# myPowerSatBoard.net
KiCad netlist of a schematic drawn in EAGLE
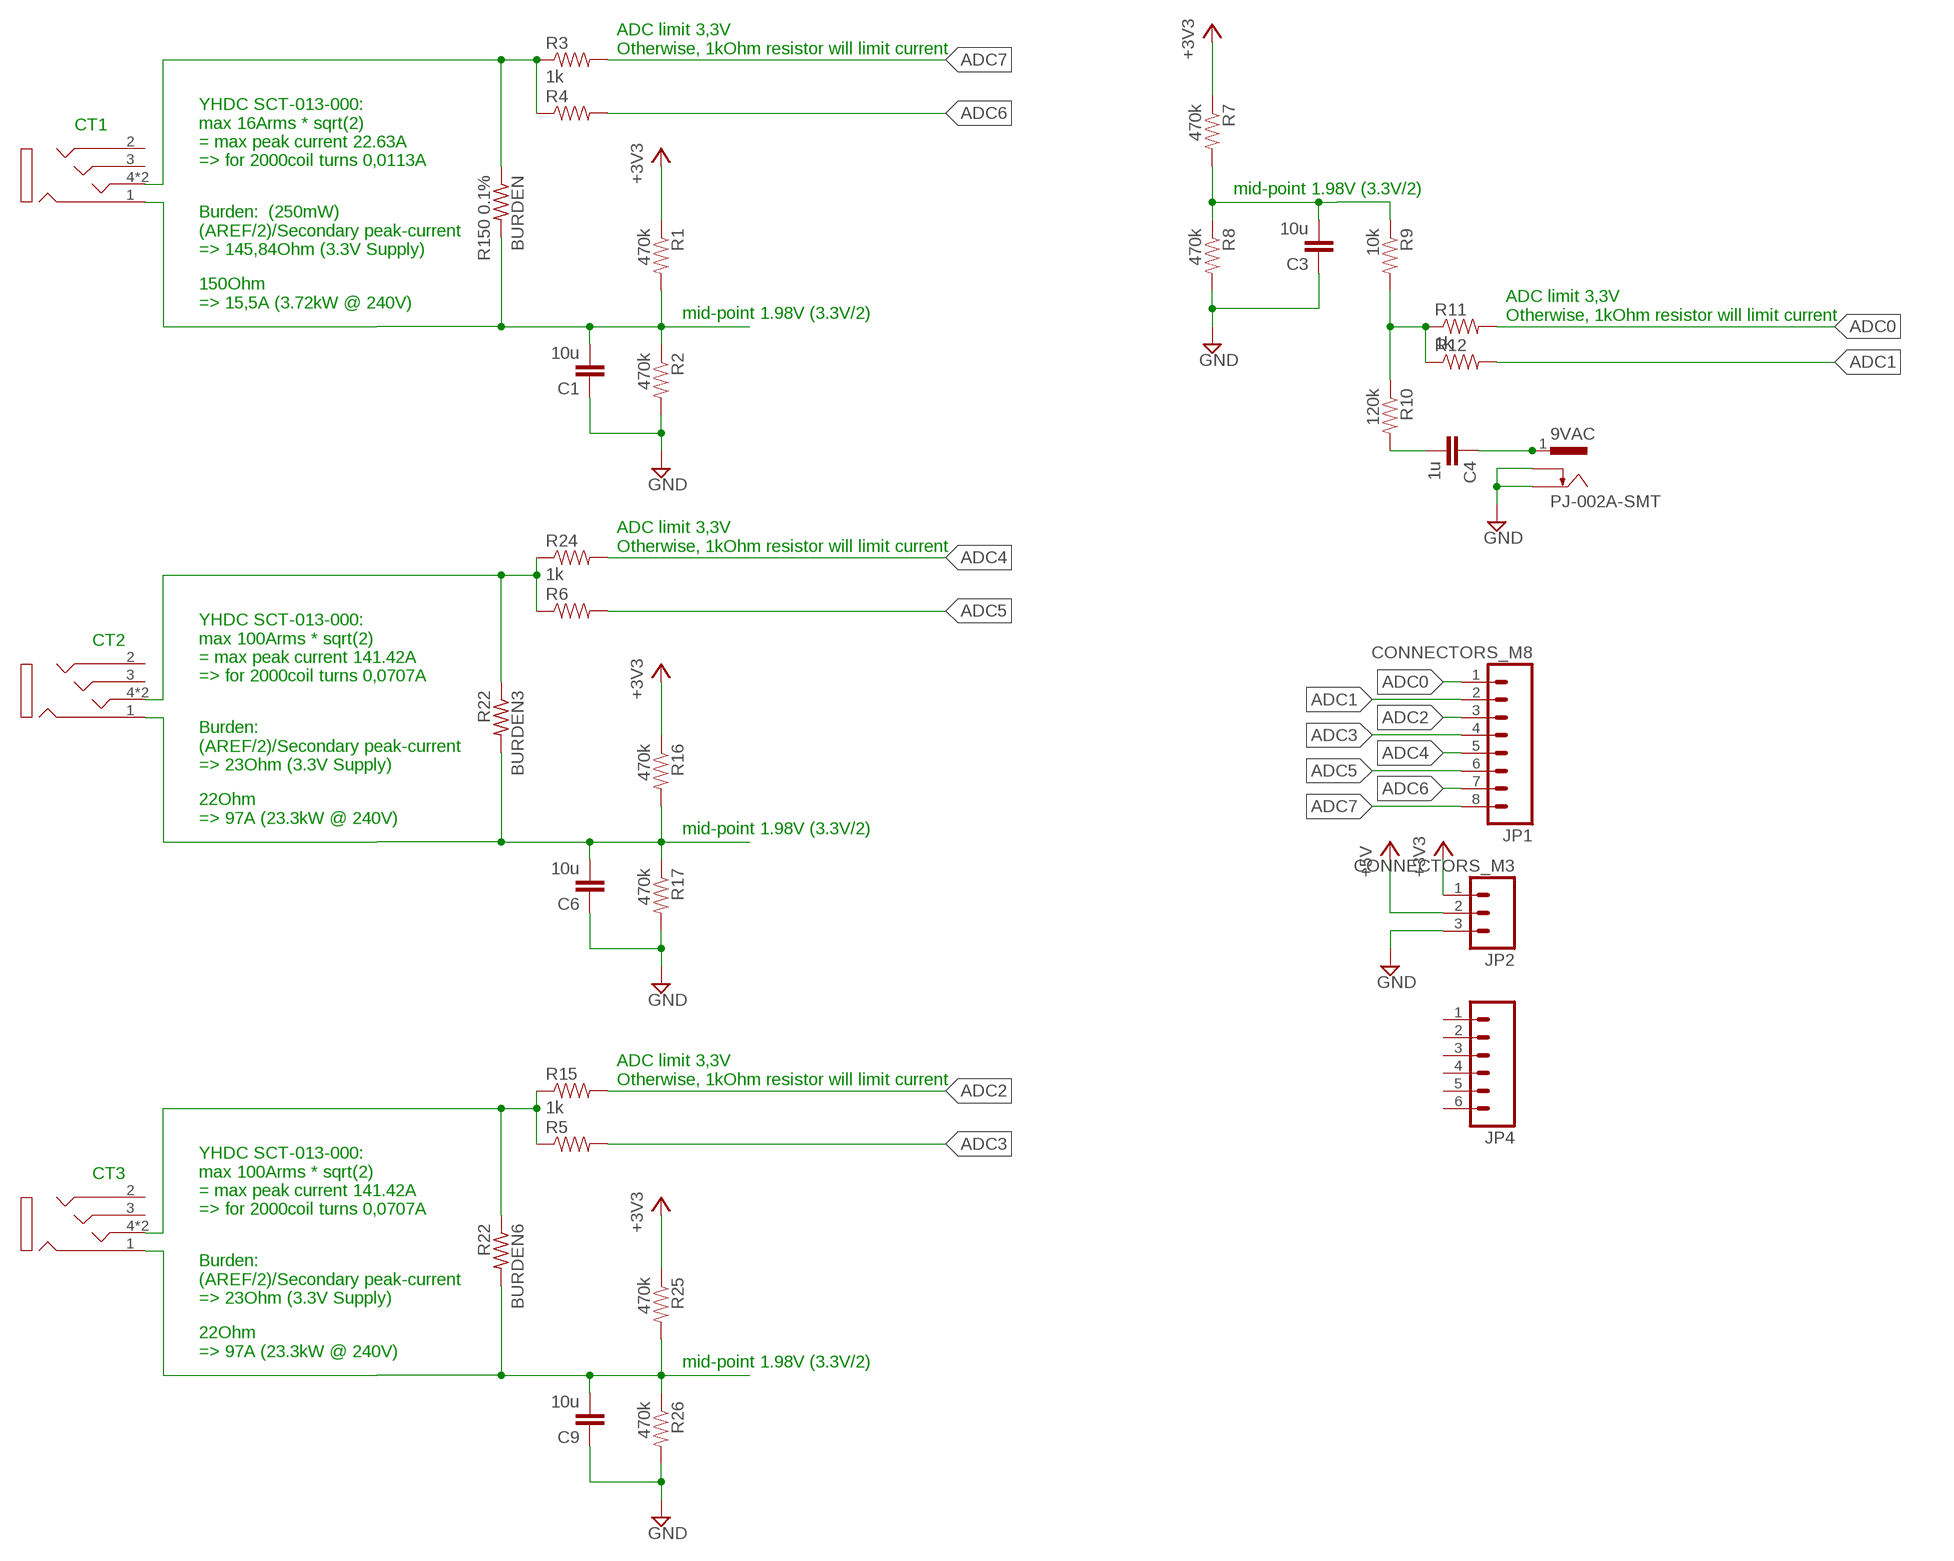
[diagram p0: schematic, sheet 1]

(export (version "E")
  (design (tool "Eeschema 10.0.6"))
  (components
    (comp (ref "9VAC")
      (value "PJ-002A-SMT")
      (footprint "eagle-import:CUI_PJ-002B-SMT")
      (libsource (lib "eagle-import") (part "PJ-002A-SMT"))
    )
    (comp (ref "BURDEN")
      (value "R150 0.1%")
      (footprint "eagle-import:R0805")
      (libsource (lib "eagle-import") (part "R-US_R0805"))
    )
    (comp (ref "BURDEN3")
      (value "R22")
      (footprint "eagle-import:R0805")
      (libsource (lib "eagle-import") (part "R-US_R0805"))
    )
    (comp (ref "BURDEN6")
      (value "R22")
      (footprint "eagle-import:R0805")
      (libsource (lib "eagle-import") (part "R-US_R0805"))
    )
    (comp (ref "C1")
      (value "10u")
      (footprint "eagle-import:0603-CAP")
      (libsource (lib "eagle-import") (part "CAP0603-CAP"))
    )
    (comp (ref "C3")
      (value "10u")
      (footprint "eagle-import:0603-CAP")
      (libsource (lib "eagle-import") (part "CAP0603-CAP"))
    )
    (comp (ref "C4")
      (value "1u")
      (footprint "eagle-import:0603-CAP")
      (libsource (lib "eagle-import") (part "CAP0603-CAP"))
    )
    (comp (ref "C6")
      (value "10u")
      (footprint "eagle-import:0603-CAP")
      (libsource (lib "eagle-import") (part "CAP0603-CAP"))
    )
    (comp (ref "C9")
      (value "10u")
      (footprint "eagle-import:0603-CAP")
      (libsource (lib "eagle-import") (part "CAP0603-CAP"))
    )
    (comp (ref "CT1")
      (value "1503_13")
      (footprint "eagle-import:1503-03")
      (libsource (lib "eagle-import") (part "1503_13"))
    )
    (comp (ref "CT4")
      (value "1503_13")
      (footprint "eagle-import:1503-03")
      (libsource (lib "eagle-import") (part "1503_13"))
    )
    (comp (ref "CT7")
      (value "1503_13")
      (footprint "eagle-import:1503-03")
      (libsource (lib "eagle-import") (part "1503_13"))
    )
    (comp (ref "JP1")
      (value "CONNECTORS_M8")
      (footprint "eagle-import:CONNECTORS_1X8")
      (libsource (lib "eagle-import") (part "CONNECTORS_M8"))
    )
    (comp (ref "JP2")
      (value "CONNECTORS_M3")
      (footprint "eagle-import:CONNECTORS_1X3")
      (libsource (lib "eagle-import") (part "CONNECTORS_M3"))
    )
    (comp (ref "JP4")
      (value "CONNECTORS_M06SIP")
      (footprint "eagle-import:CONNECTORS_1X06")
      (libsource (lib "eagle-import") (part "CONNECTORS_M06SIP"))
    )
    (comp (ref "R1")
      (value "470k")
      (footprint "eagle-import:0603-RES")
      (libsource (lib "eagle-import") (part "RESISTOR0603-RES"))
    )
    (comp (ref "R2")
      (value "470k")
      (footprint "eagle-import:0603-RES")
      (libsource (lib "eagle-import") (part "RESISTOR0603-RES"))
    )
    (comp (ref "R3")
      (value "1k")
      (footprint "eagle-import:0603-RES")
      (libsource (lib "eagle-import") (part "RESISTOR0603-RES"))
    )
    (comp (ref "R4")
      (value "RESISTOR0603-RES")
      (footprint "eagle-import:0603-RES")
      (libsource (lib "eagle-import") (part "RESISTOR0603-RES"))
    )
    (comp (ref "R5")
      (value "RESISTOR0603-RES")
      (footprint "eagle-import:0603-RES")
      (libsource (lib "eagle-import") (part "RESISTOR0603-RES"))
    )
    (comp (ref "R6")
      (value "RESISTOR0603-RES")
      (footprint "eagle-import:0603-RES")
      (libsource (lib "eagle-import") (part "RESISTOR0603-RES"))
    )
    (comp (ref "R7")
      (value "470k")
      (footprint "eagle-import:0603-RES")
      (libsource (lib "eagle-import") (part "RESISTOR0603-RES"))
    )
    (comp (ref "R8")
      (value "470k")
      (footprint "eagle-import:0603-RES")
      (libsource (lib "eagle-import") (part "RESISTOR0603-RES"))
    )
    (comp (ref "R9")
      (value "10k")
      (footprint "eagle-import:0603-RES")
      (libsource (lib "eagle-import") (part "RESISTOR0603-RES"))
    )
    (comp (ref "R10")
      (value "120k")
      (footprint "eagle-import:0603-RES")
      (libsource (lib "eagle-import") (part "RESISTOR0603-RES"))
    )
    (comp (ref "R11")
      (value "1k")
      (footprint "eagle-import:0603-RES")
      (libsource (lib "eagle-import") (part "RESISTOR0603-RES"))
    )
    (comp (ref "R12")
      (value "RESISTOR0603-RES")
      (footprint "eagle-import:0603-RES")
      (libsource (lib "eagle-import") (part "RESISTOR0603-RES"))
    )
    (comp (ref "R15")
      (value "1k")
      (footprint "eagle-import:0603-RES")
      (libsource (lib "eagle-import") (part "RESISTOR0603-RES"))
    )
    (comp (ref "R16")
      (value "470k")
      (footprint "eagle-import:0603-RES")
      (libsource (lib "eagle-import") (part "RESISTOR0603-RES"))
    )
    (comp (ref "R17")
      (value "470k")
      (footprint "eagle-import:0603-RES")
      (libsource (lib "eagle-import") (part "RESISTOR0603-RES"))
    )
    (comp (ref "R24")
      (value "1k")
      (footprint "eagle-import:0603-RES")
      (libsource (lib "eagle-import") (part "RESISTOR0603-RES"))
    )
    (comp (ref "R25")
      (value "470k")
      (footprint "eagle-import:0603-RES")
      (libsource (lib "eagle-import") (part "RESISTOR0603-RES"))
    )
    (comp (ref "R26")
      (value "470k")
      (footprint "eagle-import:0603-RES")
      (libsource (lib "eagle-import") (part "RESISTOR0603-RES"))
    )
  )
  (nets
    (net (code "1") (name "+3V3") (class "Default")
      (node (ref "JP2") (pin "1") (pinfunction "1_1") (pintype "passive"))
      (node (ref "R1") (pin "1") (pinfunction "1_1") (pintype "passive"))
      (node (ref "R16") (pin "1") (pinfunction "1_1") (pintype "passive"))
      (node (ref "R25") (pin "1") (pinfunction "1_1") (pintype "passive"))
      (node (ref "R7") (pin "1") (pinfunction "1_1") (pintype "passive"))
    )
    (net (code "2") (name "+5V") (class "Default")
      (node (ref "JP2") (pin "2") (pinfunction "2_2") (pintype "passive"))
    )
    (net (code "3") (name "ADC0") (class "Default")
      (node (ref "JP1") (pin "1") (pinfunction "1_1") (pintype "passive"))
      (node (ref "R11") (pin "2") (pinfunction "2_2") (pintype "passive"))
    )
    (net (code "4") (name "ADC1") (class "Default")
      (node (ref "JP1") (pin "2") (pinfunction "2_2") (pintype "passive"))
      (node (ref "R12") (pin "2") (pinfunction "2_2") (pintype "passive"))
    )
    (net (code "5") (name "ADC2") (class "Default")
      (node (ref "JP1") (pin "3") (pinfunction "3_3") (pintype "passive"))
      (node (ref "R15") (pin "2") (pinfunction "2_2") (pintype "passive"))
    )
    (net (code "6") (name "ADC3") (class "Default")
      (node (ref "JP1") (pin "4") (pinfunction "4_4") (pintype "passive"))
      (node (ref "R5") (pin "2") (pinfunction "2_2") (pintype "passive"))
    )
    (net (code "7") (name "ADC4") (class "Default")
      (node (ref "JP1") (pin "5") (pinfunction "5_5") (pintype "passive"))
      (node (ref "R24") (pin "2") (pinfunction "2_2") (pintype "passive"))
    )
    (net (code "8") (name "ADC5") (class "Default")
      (node (ref "JP1") (pin "6") (pinfunction "6_6") (pintype "passive"))
      (node (ref "R6") (pin "2") (pinfunction "2_2") (pintype "passive"))
    )
    (net (code "9") (name "ADC6") (class "Default")
      (node (ref "JP1") (pin "7") (pinfunction "7_7") (pintype "passive"))
      (node (ref "R4") (pin "2") (pinfunction "2_2") (pintype "passive"))
    )
    (net (code "10") (name "ADC7") (class "Default")
      (node (ref "JP1") (pin "8") (pinfunction "8_8") (pintype "passive"))
      (node (ref "R3") (pin "2") (pinfunction "2_2") (pintype "passive"))
    )
    (net (code "11") (name "GND") (class "Default")
      (node (ref "9VAC") (pin "3") (pinfunction "3_3") (pintype "passive"))
      (node (ref "9VAC") (pin "4") (pinfunction "4_4") (pintype "passive"))
      (node (ref "C1") (pin "1") (pinfunction "1_1") (pintype "passive"))
      (node (ref "C3") (pin "1") (pinfunction "1_1") (pintype "passive"))
      (node (ref "C6") (pin "1") (pinfunction "1_1") (pintype "passive"))
      (node (ref "C9") (pin "1") (pinfunction "1_1") (pintype "passive"))
      (node (ref "JP2") (pin "3") (pinfunction "3_3") (pintype "passive"))
      (node (ref "R17") (pin "2") (pinfunction "2_2") (pintype "passive"))
      (node (ref "R2") (pin "2") (pinfunction "2_2") (pintype "passive"))
      (node (ref "R26") (pin "2") (pinfunction "2_2") (pintype "passive"))
      (node (ref "R8") (pin "2") (pinfunction "2_2") (pintype "passive"))
    )
    (net (code "12") (name "Net-(9VAC-Pad1)") (class "Default")
      (node (ref "9VAC") (pin "1") (pinfunction "1_1") (pintype "passive"))
      (node (ref "9VAC") (pin "2") (pinfunction "2_2") (pintype "passive"))
      (node (ref "C4") (pin "1") (pinfunction "1_1") (pintype "passive"))
    )
    (net (code "13") (name "Net-(BURDEN-Pad1)") (class "Default")
      (node (ref "BURDEN") (pin "1") (pinfunction "1_1") (pintype "passive"))
      (node (ref "CT1") (pin "4") (pinfunction "4_4") (pintype "bidirectional"))
      (node (ref "CT1") (pin "4-2") (pinfunction "4_4-2") (pintype "bidirectional"))
      (node (ref "R3") (pin "1") (pinfunction "1_1") (pintype "passive"))
      (node (ref "R4") (pin "1") (pinfunction "1_1") (pintype "passive"))
    )
    (net (code "14") (name "Net-(BURDEN-Pad2)") (class "Default")
      (node (ref "BURDEN") (pin "2") (pinfunction "2_2") (pintype "passive"))
      (node (ref "C1") (pin "2") (pinfunction "2_2") (pintype "passive"))
      (node (ref "CT1") (pin "1") (pinfunction "1_1") (pintype "bidirectional"))
      (node (ref "R1") (pin "2") (pinfunction "2_2") (pintype "passive"))
      (node (ref "R2") (pin "1") (pinfunction "1_1") (pintype "passive"))
    )
    (net (code "15") (name "Net-(BURDEN3-Pad1)") (class "Default")
      (node (ref "BURDEN3") (pin "1") (pinfunction "1_1") (pintype "passive"))
      (node (ref "CT4") (pin "4") (pinfunction "4_4") (pintype "bidirectional"))
      (node (ref "CT4") (pin "4-2") (pinfunction "4_4-2") (pintype "bidirectional"))
      (node (ref "R24") (pin "1") (pinfunction "1_1") (pintype "passive"))
      (node (ref "R6") (pin "1") (pinfunction "1_1") (pintype "passive"))
    )
    (net (code "16") (name "Net-(BURDEN3-Pad2)") (class "Default")
      (node (ref "BURDEN3") (pin "2") (pinfunction "2_2") (pintype "passive"))
      (node (ref "C6") (pin "2") (pinfunction "2_2") (pintype "passive"))
      (node (ref "CT4") (pin "1") (pinfunction "1_1") (pintype "bidirectional"))
      (node (ref "R16") (pin "2") (pinfunction "2_2") (pintype "passive"))
      (node (ref "R17") (pin "1") (pinfunction "1_1") (pintype "passive"))
    )
    (net (code "17") (name "Net-(BURDEN6-Pad1)") (class "Default")
      (node (ref "BURDEN6") (pin "1") (pinfunction "1_1") (pintype "passive"))
      (node (ref "CT7") (pin "4") (pinfunction "4_4") (pintype "bidirectional"))
      (node (ref "CT7") (pin "4-2") (pinfunction "4_4-2") (pintype "bidirectional"))
      (node (ref "R15") (pin "1") (pinfunction "1_1") (pintype "passive"))
      (node (ref "R5") (pin "1") (pinfunction "1_1") (pintype "passive"))
    )
    (net (code "18") (name "Net-(BURDEN6-Pad2)") (class "Default")
      (node (ref "BURDEN6") (pin "2") (pinfunction "2_2") (pintype "passive"))
      (node (ref "C9") (pin "2") (pinfunction "2_2") (pintype "passive"))
      (node (ref "CT7") (pin "1") (pinfunction "1_1") (pintype "bidirectional"))
      (node (ref "R25") (pin "2") (pinfunction "2_2") (pintype "passive"))
      (node (ref "R26") (pin "1") (pinfunction "1_1") (pintype "passive"))
    )
    (net (code "19") (name "Net-(C3-Pad2)") (class "Default")
      (node (ref "C3") (pin "2") (pinfunction "2_2") (pintype "passive"))
      (node (ref "R7") (pin "2") (pinfunction "2_2") (pintype "passive"))
      (node (ref "R8") (pin "1") (pinfunction "1_1") (pintype "passive"))
      (node (ref "R9") (pin "1") (pinfunction "1_1") (pintype "passive"))
    )
    (net (code "20") (name "Net-(C4-Pad2)") (class "Default")
      (node (ref "C4") (pin "2") (pinfunction "2_2") (pintype "passive"))
      (node (ref "R10") (pin "2") (pinfunction "2_2") (pintype "passive"))
    )
    (net (code "21") (name "Net-(R10-Pad1)") (class "Default")
      (node (ref "R10") (pin "1") (pinfunction "1_1") (pintype "passive"))
      (node (ref "R11") (pin "1") (pinfunction "1_1") (pintype "passive"))
      (node (ref "R12") (pin "1") (pinfunction "1_1") (pintype "passive"))
      (node (ref "R9") (pin "2") (pinfunction "2_2") (pintype "passive"))
    )
    (net (code "22") (name "unconnected-(CT1-Pad2)") (class "Default")
      (node (ref "CT1") (pin "2") (pinfunction "2_2") (pintype "bidirectional"))
    )
    (net (code "23") (name "unconnected-(CT1-Pad3)") (class "Default")
      (node (ref "CT1") (pin "3") (pinfunction "3_3") (pintype "bidirectional"))
    )
    (net (code "24") (name "unconnected-(CT4-Pad2)") (class "Default")
      (node (ref "CT4") (pin "2") (pinfunction "2_2") (pintype "bidirectional"))
    )
    (net (code "25") (name "unconnected-(CT4-Pad3)") (class "Default")
      (node (ref "CT4") (pin "3") (pinfunction "3_3") (pintype "bidirectional"))
    )
    (net (code "26") (name "unconnected-(CT7-Pad2)") (class "Default")
      (node (ref "CT7") (pin "2") (pinfunction "2_2") (pintype "bidirectional"))
    )
    (net (code "27") (name "unconnected-(CT7-Pad3)") (class "Default")
      (node (ref "CT7") (pin "3") (pinfunction "3_3") (pintype "bidirectional"))
    )
    (net (code "28") (name "unconnected-(JP4-Pad1)") (class "Default")
      (node (ref "JP4") (pin "1") (pinfunction "1_1") (pintype "passive"))
    )
    (net (code "29") (name "unconnected-(JP4-Pad2)") (class "Default")
      (node (ref "JP4") (pin "2") (pinfunction "2_2") (pintype "passive"))
    )
    (net (code "30") (name "unconnected-(JP4-Pad3)") (class "Default")
      (node (ref "JP4") (pin "3") (pinfunction "3_3") (pintype "passive"))
    )
    (net (code "31") (name "unconnected-(JP4-Pad4)") (class "Default")
      (node (ref "JP4") (pin "4") (pinfunction "4_4") (pintype "passive"))
    )
    (net (code "32") (name "unconnected-(JP4-Pad5)") (class "Default")
      (node (ref "JP4") (pin "5") (pinfunction "5_5") (pintype "passive"))
    )
    (net (code "33") (name "unconnected-(JP4-Pad6)") (class "Default")
      (node (ref "JP4") (pin "6") (pinfunction "6_6") (pintype "passive"))
    )
  )
)
